# ThreadModule.net
KiCad netlist of a schematic drawn in Altium Designer
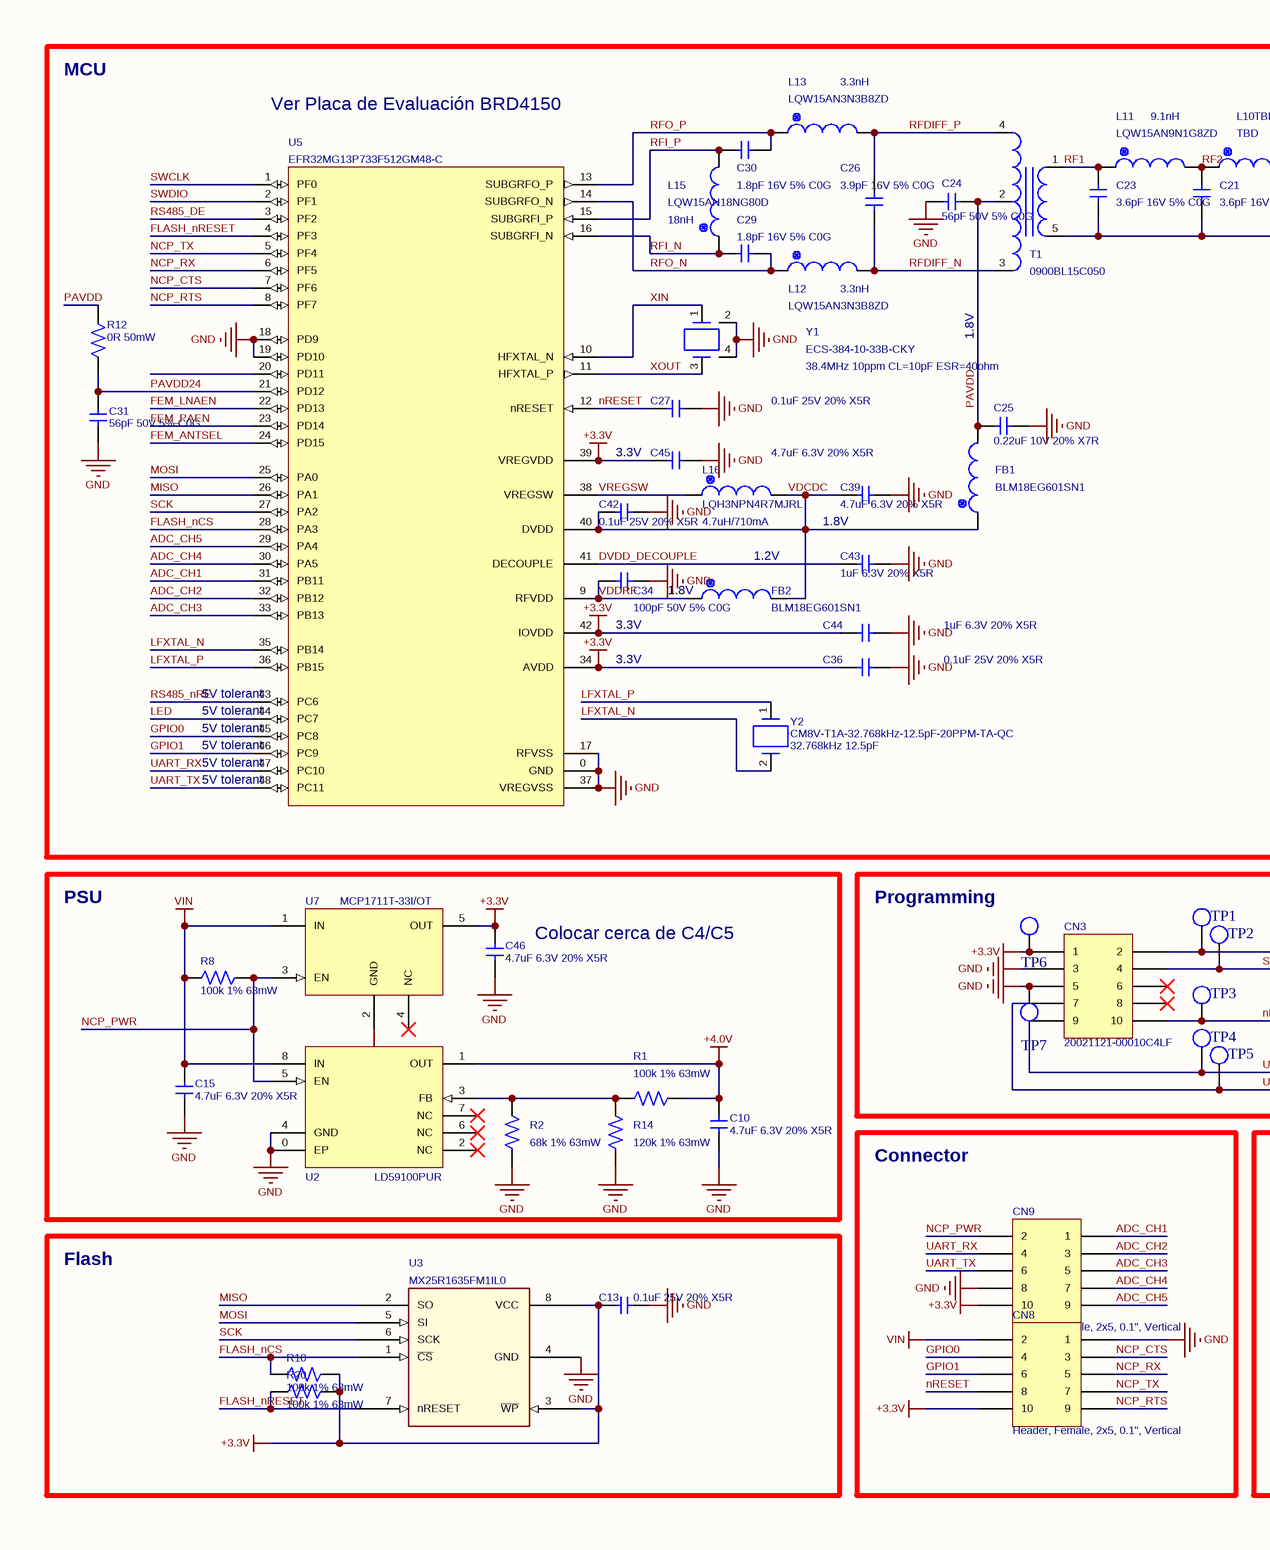
[diagram p0: ThreadModule.SchDoc, left]
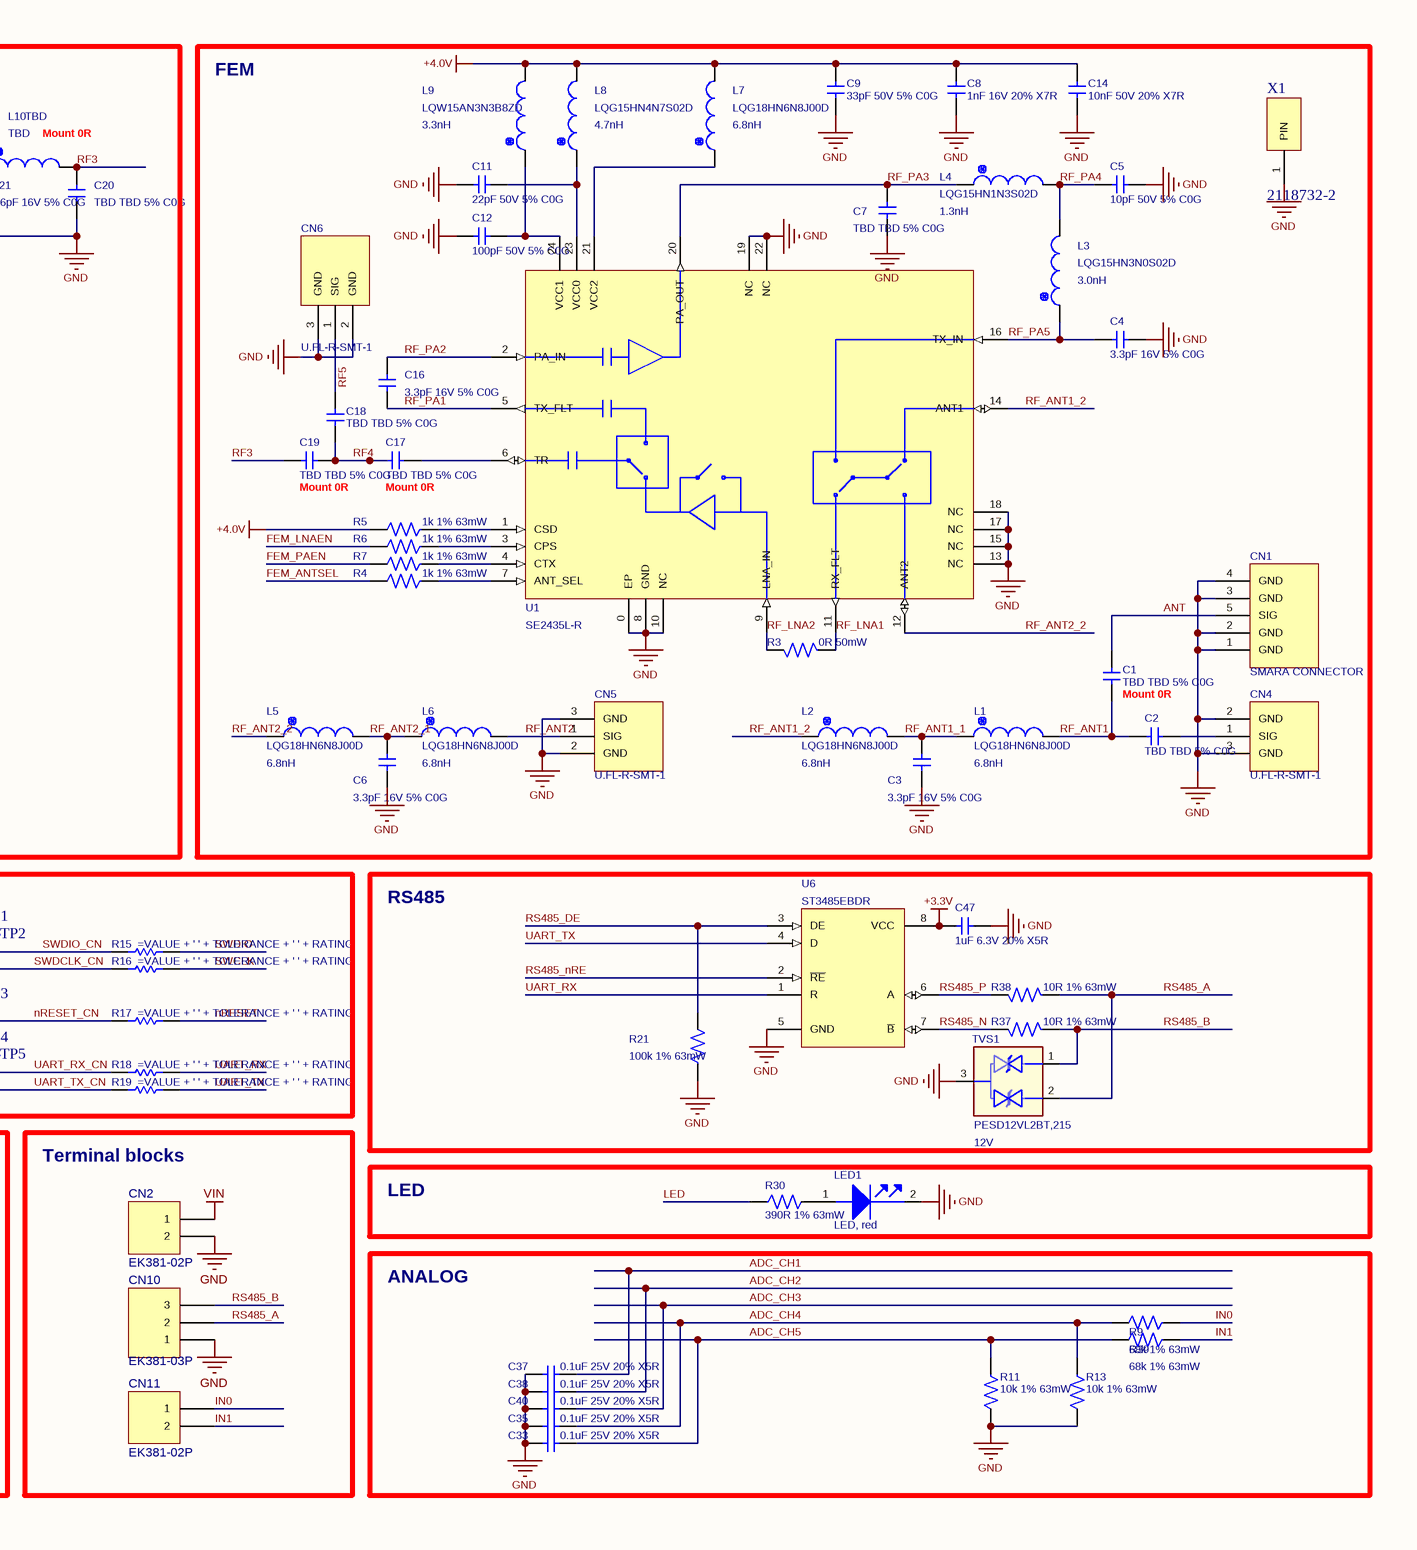
[diagram p1: ThreadModule.SchDoc, right]

(export (version "E")
  (design (tool "Eeschema 10.0.6"))
  (components
    (comp (ref "C1")
      (value "TBD TBD 5% C0G")
      (footprint "CAPC1005X55L")
      (description "Capacitor, ceramic")
      (fields
        (field (name "MFG") "<GENERIC>")
        (field (name "ASSEMBLYCOMMENTS") "Mount 0R")
        (field (name "TOLERANCE") "5%")
        (field (name "FOOTPRINT CHECKED") "Assign OK, Footprint OK")
      )
      (libsource (lib "*") (part "C_Dup1"))
    )
    (comp (ref "C2")
      (value "TBD TBD 5% C0G")
      (footprint "CAPC1005X55L")
      (description "Capacitor, ceramic")
      (fields
        (field (name "MFG") "<GENERIC>")
        (field (name "TOLERANCE") "5%")
        (field (name "FOOTPRINT CHECKED") "Assign OK, Footprint OK")
      )
      (libsource (lib "*") (part "C_Dup1"))
    )
    (comp (ref "C3")
      (value "3.3pF 16V 5% C0G")
      (footprint "CAPC1005X55L")
      (description "Capacitor, ceramic")
      (fields
        (field (name "MFG") "YAGEO")
        (field (name "TOLERANCE") "5%")
        (field (name "FOOTPRINT CHECKED") "Assign OK, Footprint OK")
      )
      (libsource (lib "*") (part "C_Dup1"))
    )
    (comp (ref "C4")
      (value "3.3pF 16V 5% C0G")
      (footprint "CAPC1005X55L")
      (description "Capacitor, ceramic")
      (fields
        (field (name "MFG") "YAGEO")
        (field (name "TOLERANCE") "5%")
        (field (name "FOOTPRINT CHECKED") "Assign OK, Footprint OK")
      )
      (libsource (lib "*") (part "C_Dup1"))
    )
    (comp (ref "C5")
      (value "10pF 50V 5% C0G")
      (footprint "CAPC1005X55L")
      (description "Capacitor, ceramic")
      (fields
        (field (name "MFG") "SAMSUNG")
        (field (name "TOLERANCE") "5%")
        (field (name "FOOTPRINT CHECKED") "Assign OK, Footprint OK")
      )
      (libsource (lib "*") (part "C_Dup1"))
    )
    (comp (ref "C6")
      (value "3.3pF 16V 5% C0G")
      (footprint "CAPC1005X55L")
      (description "Capacitor, ceramic")
      (fields
        (field (name "MFG") "YAGEO")
        (field (name "TOLERANCE") "5%")
        (field (name "FOOTPRINT CHECKED") "Assign OK, Footprint OK")
      )
      (libsource (lib "*") (part "C_Dup1"))
    )
    (comp (ref "C7")
      (value "TBD TBD 5% C0G")
      (footprint "CAPC1005X55L")
      (description "Capacitor, ceramic")
      (fields
        (field (name "MFG") "<GENERIC>")
        (field (name "TOLERANCE") "5%")
        (field (name "FOOTPRINT CHECKED") "Assign OK, Footprint OK")
      )
      (libsource (lib "*") (part "C_Dup1"))
    )
    (comp (ref "C8")
      (value "1nF 16V 20% X7R")
      (footprint "CAPC1005X55L")
      (description "Capacitor, ceramic")
      (fields
        (field (name "MFG") "SAMSUNG")
        (field (name "TOLERANCE") "20%")
        (field (name "FOOTPRINT CHECKED") "Assign OK, Footprint OK")
      )
      (libsource (lib "*") (part "C_Dup1"))
    )
    (comp (ref "C9")
      (value "33pF 50V 5% C0G")
      (footprint "CAPC1005X55L")
      (description "Capacitor, ceramic")
      (fields
        (field (name "MFG") "SAMSUNG")
        (field (name "TOLERANCE") "5%")
        (field (name "FOOTPRINT CHECKED") "Assign OK, Footprint OK")
      )
      (libsource (lib "*") (part "C_Dup1"))
    )
    (comp (ref "C10")
      (value "4.7uF 6.3V 20% X5R")
      (footprint "CAPC1608X90N")
      (description "Capacitor, ceramic")
      (fields
        (field (name "MFG") "SAMSUNG")
        (field (name "TOLERANCE") "20%")
        (field (name "FOOTPRINT CHECKED") "Assign OK, Footprint OK")
      )
      (libsource (lib "*") (part "C_Dup1"))
    )
    (comp (ref "C11")
      (value "22pF 50V 5% C0G")
      (footprint "CAPC1005X55L")
      (description "Capacitor, ceramic")
      (fields
        (field (name "MFG") "SAMSUNG")
        (field (name "TOLERANCE") "5%")
        (field (name "FOOTPRINT CHECKED") "Assign OK, Footprint OK")
      )
      (libsource (lib "*") (part "C_Dup1"))
    )
    (comp (ref "C12")
      (value "100pF 50V 5% C0G")
      (footprint "CAPC1005X55L")
      (description "Capacitor, ceramic")
      (fields
        (field (name "MFG") "SAMSUNG")
        (field (name "TOLERANCE") "5%")
        (field (name "FOOTPRINT CHECKED") "Assign OK, Footprint OK")
      )
      (libsource (lib "*") (part "C_Dup1"))
    )
    (comp (ref "C13")
      (value "0.1uF 25V 20% X5R")
      (footprint "CAPC1005N")
      (description "Capacitor, ceramic")
      (fields
        (field (name "MFG") "SAMSUNG")
        (field (name "TOLERANCE") "20%")
        (field (name "FOOTPRINT CHECKED") "Assign OK, Footprint OK")
      )
      (libsource (lib "*") (part "C_Dup1"))
    )
    (comp (ref "C14")
      (value "10nF 50V 20% X7R")
      (footprint "CAPC1005X55L")
      (description "Capacitor, ceramic")
      (fields
        (field (name "MFG") "SAMSUNG")
        (field (name "TOLERANCE") "20%")
        (field (name "FOOTPRINT CHECKED") "Assign OK, Footprint OK")
      )
      (libsource (lib "*") (part "C_Dup1"))
    )
    (comp (ref "C15")
      (value "4.7uF 6.3V 20% X5R")
      (footprint "CAPC1608X90N")
      (description "Capacitor, ceramic")
      (fields
        (field (name "MFG") "SAMSUNG")
        (field (name "TOLERANCE") "20%")
        (field (name "FOOTPRINT CHECKED") "Assign OK, Footprint OK")
      )
      (libsource (lib "*") (part "C_Dup1"))
    )
    (comp (ref "C16")
      (value "3.3pF 16V 5% C0G")
      (footprint "CAPC1005X55L")
      (description "Capacitor, ceramic")
      (fields
        (field (name "MFG") "YAGEO")
        (field (name "TOLERANCE") "5%")
        (field (name "FOOTPRINT CHECKED") "Assign OK, Footprint OK")
      )
      (libsource (lib "*") (part "C_Dup1"))
    )
    (comp (ref "C17")
      (value "TBD TBD 5% C0G")
      (footprint "CAPC1005X55L")
      (description "Capacitor, ceramic")
      (fields
        (field (name "MFG") "<GENERIC>")
        (field (name "ASSEMBLYCOMMENTS") "Mount 0R")
        (field (name "TOLERANCE") "5%")
        (field (name "FOOTPRINT CHECKED") "Assign OK, Footprint OK")
      )
      (libsource (lib "*") (part "C_Dup1"))
    )
    (comp (ref "C18")
      (value "TBD TBD 5% C0G")
      (footprint "CAPC1005X55L")
      (description "Capacitor, ceramic")
      (fields
        (field (name "MFG") "<GENERIC>")
        (field (name "TOLERANCE") "5%")
        (field (name "FOOTPRINT CHECKED") "Assign OK, Footprint OK")
      )
      (libsource (lib "*") (part "C_Dup1"))
    )
    (comp (ref "C19")
      (value "TBD TBD 5% C0G")
      (footprint "CAPC1005X55L")
      (description "Capacitor, ceramic")
      (fields
        (field (name "MFG") "<GENERIC>")
        (field (name "ASSEMBLYCOMMENTS") "Mount 0R")
        (field (name "TOLERANCE") "5%")
        (field (name "FOOTPRINT CHECKED") "Assign OK, Footprint OK")
      )
      (libsource (lib "*") (part "C_Dup1"))
    )
    (comp (ref "C20")
      (value "TBD TBD 5% C0G")
      (footprint "CAPC1005X55L")
      (description "Capacitor, ceramic")
      (fields
        (field (name "MFG") "<GENERIC>")
        (field (name "TOLERANCE") "5%")
        (field (name "FOOTPRINT CHECKED") "Assign OK, Footprint OK")
      )
      (libsource (lib "*") (part "C_Dup1"))
    )
    (comp (ref "C21")
      (value "3.6pF 16V 5% C0G")
      (footprint "CAPC1005X55L")
      (description "Capacitor, ceramic")
      (fields
        (field (name "MFG") "YAGEO")
        (field (name "TOLERANCE") "5%")
        (field (name "FOOTPRINT CHECKED") "Assign OK, Footprint OK")
      )
      (libsource (lib "*") (part "C_Dup1"))
    )
    (comp (ref "C23")
      (value "3.6pF 16V 5% C0G")
      (footprint "CAPC1005X55L")
      (description "Capacitor, ceramic")
      (fields
        (field (name "MFG") "YAGEO")
        (field (name "TOLERANCE") "5%")
        (field (name "FOOTPRINT CHECKED") "Assign OK, Footprint OK")
      )
      (libsource (lib "*") (part "C_Dup1"))
    )
    (comp (ref "C24")
      (value "56pF 50V 5% C0G")
      (footprint "CAPC1005X55L")
      (description "Capacitor, ceramic")
      (fields
        (field (name "MFG") "SAMSUNG")
        (field (name "TOLERANCE") "5%")
        (field (name "FOOTPRINT CHECKED") "Assign OK, Footprint OK")
      )
      (libsource (lib "*") (part "C_Dup1"))
    )
    (comp (ref "C25")
      (value "0.22uF 10V 20% X7R")
      (footprint "CAPC1005N")
      (description "Capacitor, ceramic")
      (fields
        (field (name "MFG") "SAMSUNG")
        (field (name "TOLERANCE") "20%")
        (field (name "FOOTPRINT CHECKED") "Assign OK, Footprint OK")
      )
      (libsource (lib "*") (part "C_Dup1"))
    )
    (comp (ref "C26")
      (value "3.9pF 16V 5% C0G")
      (footprint "CAPC1005X55L")
      (description "Capacitor, ceramic")
      (fields
        (field (name "MFG") "YAGEO")
        (field (name "TOLERANCE") "5%")
        (field (name "FOOTPRINT CHECKED") "Assign OK, Footprint OK")
      )
      (libsource (lib "*") (part "C_Dup1"))
    )
    (comp (ref "C27")
      (value "0.1uF 25V 20% X5R")
      (footprint "CAPC1005N")
      (description "Capacitor, ceramic")
      (fields
        (field (name "MFG") "SAMSUNG")
        (field (name "TOLERANCE") "20%")
        (field (name "FOOTPRINT CHECKED") "Assign OK, Footprint OK")
      )
      (libsource (lib "*") (part "C_Dup1"))
    )
    (comp (ref "C29")
      (value "1.8pF 16V 5% C0G")
      (footprint "CAPC1005X55L")
      (description "Capacitor, ceramic")
      (fields
        (field (name "MFG") "YAGEO")
        (field (name "TOLERANCE") "5%")
        (field (name "FOOTPRINT CHECKED") "Assign OK, Footprint OK")
      )
      (libsource (lib "*") (part "C_Dup1"))
    )
    (comp (ref "C30")
      (value "1.8pF 16V 5% C0G")
      (footprint "CAPC1005X55L")
      (description "Capacitor, ceramic")
      (fields
        (field (name "MFG") "YAGEO")
        (field (name "TOLERANCE") "5%")
        (field (name "FOOTPRINT CHECKED") "Assign OK, Footprint OK")
      )
      (libsource (lib "*") (part "C_Dup1"))
    )
    (comp (ref "C31")
      (value "56pF 50V 5% C0G")
      (footprint "CAPC1005X55L")
      (description "Capacitor, ceramic")
      (fields
        (field (name "MFG") "SAMSUNG")
        (field (name "TOLERANCE") "5%")
        (field (name "FOOTPRINT CHECKED") "Assign OK, Footprint OK")
      )
      (libsource (lib "*") (part "C_Dup1"))
    )
    (comp (ref "C33")
      (value "0.1uF 25V 20% X5R")
      (footprint "CAPC1005N")
      (description "Capacitor, ceramic")
      (fields
        (field (name "MFG") "SAMSUNG")
        (field (name "TOLERANCE") "20%")
        (field (name "FOOTPRINT CHECKED") "Assign OK, Footprint OK")
      )
      (libsource (lib "*") (part "C_Dup1"))
    )
    (comp (ref "C34")
      (value "100pF 50V 5% C0G")
      (footprint "CAPC1005X55L")
      (description "Capacitor, ceramic")
      (fields
        (field (name "MFG") "SAMSUNG")
        (field (name "TOLERANCE") "5%")
        (field (name "FOOTPRINT CHECKED") "Assign OK, Footprint OK")
      )
      (libsource (lib "*") (part "C_Dup1"))
    )
    (comp (ref "C35")
      (value "0.1uF 25V 20% X5R")
      (footprint "CAPC1005N")
      (description "Capacitor, ceramic")
      (fields
        (field (name "MFG") "SAMSUNG")
        (field (name "TOLERANCE") "20%")
        (field (name "FOOTPRINT CHECKED") "Assign OK, Footprint OK")
      )
      (libsource (lib "*") (part "C_Dup1"))
    )
    (comp (ref "C36")
      (value "0.1uF 25V 20% X5R")
      (footprint "CAPC1005N")
      (description "Capacitor, ceramic")
      (fields
        (field (name "MFG") "SAMSUNG")
        (field (name "TOLERANCE") "20%")
        (field (name "FOOTPRINT CHECKED") "Assign OK, Footprint OK")
      )
      (libsource (lib "*") (part "C_Dup1"))
    )
    (comp (ref "C37")
      (value "0.1uF 25V 20% X5R")
      (footprint "CAPC1005N")
      (description "Capacitor, ceramic")
      (fields
        (field (name "MFG") "SAMSUNG")
        (field (name "TOLERANCE") "20%")
        (field (name "FOOTPRINT CHECKED") "Assign OK, Footprint OK")
      )
      (libsource (lib "*") (part "C_Dup1"))
    )
    (comp (ref "C38")
      (value "0.1uF 25V 20% X5R")
      (footprint "CAPC1005N")
      (description "Capacitor, ceramic")
      (fields
        (field (name "MFG") "SAMSUNG")
        (field (name "TOLERANCE") "20%")
        (field (name "FOOTPRINT CHECKED") "Assign OK, Footprint OK")
      )
      (libsource (lib "*") (part "C_Dup1"))
    )
    (comp (ref "C39")
      (value "4.7uF 6.3V 20% X5R")
      (footprint "CAPC1608X90N")
      (description "Capacitor, ceramic")
      (fields
        (field (name "MFG") "SAMSUNG")
        (field (name "TOLERANCE") "20%")
        (field (name "FOOTPRINT CHECKED") "Assign OK, Footprint OK")
      )
      (libsource (lib "*") (part "C_Dup1"))
    )
    (comp (ref "C40")
      (value "0.1uF 25V 20% X5R")
      (footprint "CAPC1005N")
      (description "Capacitor, ceramic")
      (fields
        (field (name "MFG") "SAMSUNG")
        (field (name "TOLERANCE") "20%")
        (field (name "FOOTPRINT CHECKED") "Assign OK, Footprint OK")
      )
      (libsource (lib "*") (part "C_Dup1"))
    )
    (comp (ref "C42")
      (value "0.1uF 25V 20% X5R")
      (footprint "CAPC1005N")
      (description "Capacitor, ceramic")
      (fields
        (field (name "MFG") "SAMSUNG")
        (field (name "TOLERANCE") "20%")
        (field (name "FOOTPRINT CHECKED") "Assign OK, Footprint OK")
      )
      (libsource (lib "*") (part "C_Dup1"))
    )
    (comp (ref "C43")
      (value "1uF 6.3V 20% X5R")
      (footprint "CAPC1005N")
      (description "Capacitor, ceramic")
      (fields
        (field (name "MFG") "SAMSUNG")
        (field (name "TOLERANCE") "20%")
        (field (name "FOOTPRINT CHECKED") "Assign OK, Footprint OK")
      )
      (libsource (lib "*") (part "C_Dup1"))
    )
    (comp (ref "C44")
      (value "1uF 6.3V 20% X5R")
      (footprint "CAPC1005N")
      (description "Capacitor, ceramic")
      (fields
        (field (name "MFG") "SAMSUNG")
        (field (name "TOLERANCE") "20%")
        (field (name "FOOTPRINT CHECKED") "Assign OK, Footprint OK")
      )
      (libsource (lib "*") (part "C_Dup1"))
    )
    (comp (ref "C45")
      (value "4.7uF 6.3V 20% X5R")
      (footprint "CAPC1608X90N")
      (description "Capacitor, ceramic")
      (fields
        (field (name "MFG") "SAMSUNG")
        (field (name "TOLERANCE") "20%")
        (field (name "FOOTPRINT CHECKED") "Assign OK, Footprint OK")
      )
      (libsource (lib "*") (part "C_Dup1"))
    )
    (comp (ref "C46")
      (value "4.7uF 6.3V 20% X5R")
      (footprint "CAPC1608X90N")
      (description "Capacitor, ceramic")
      (fields
        (field (name "MFG") "SAMSUNG")
        (field (name "TOLERANCE") "20%")
        (field (name "FOOTPRINT CHECKED") "Assign OK, Footprint OK")
      )
      (libsource (lib "*") (part "C_Dup1"))
    )
    (comp (ref "C47")
      (value "1uF 6.3V 20% X5R")
      (footprint "CAPC1005N")
      (description "Capacitor, ceramic")
      (fields
        (field (name "MFG") "SAMSUNG")
        (field (name "TOLERANCE") "20%")
        (field (name "FOOTPRINT CHECKED") "Assign OK, Footprint OK")
      )
      (libsource (lib "*") (part "C_Dup1"))
    )
    (comp (ref "CN1")
      (value "SMARA CONNECTOR")
      (footprint "0733910320")
      (description "SMA, Right angle")
      (fields (field (name "MFG") "LPRS") (field (name "FOOTPRINT CHECKED") "Assign OK, Footprint OK"))
      (libsource (lib "xct") (part "RPSMA"))
    )
    (comp (ref "CN2")
      (value "EK381-02P")
      (footprint "EK381-02P")
      (description "Header, 2-Pin")
      (fields (field (name "MFG") "DINKLE") (field (name "FOOTPRINT CHECKED") "Assign OK, Footprint OK"))
      (libsource (lib "Miscellaneous Connectors") (part "Header 2"))
    )
    (comp (ref "CN3")
      (value "20021121-00010C4LF")
      (footprint "SensorWireless:HDR2X5")
      (description "Connector Header Surface Mount 10 position 0.050\" (1.27mm)")
      (fields (field (name "MFG") "AMPHENOL") (field (name "FOOTPRINT CHECKED") "Assign Ok, Footprint Ok"))
      (libsource (lib "Miscellaneous Connectors") (part "Header 5X2"))
    )
    (comp (ref "CN4")
      (value "U.FL-R-SMT-1")
      (footprint "U.FL-R-SMT-1")
      (description "Ultra Small Surface Mount Coaxial Connectors - 1.9mm or 2.4mm Mated Height")
      (fields (field (name "MFG") "HIROSE") (field (name "FOOTPRINT CHECKED") "Assign OK, Footprint OK"))
      (libsource (lib "traz") (part "U.FL-R-SMT-1"))
    )
    (comp (ref "CN5")
      (value "U.FL-R-SMT-1")
      (footprint "U.FL-R-SMT-1")
      (description "Ultra Small Surface Mount Coaxial Connectors - 1.9mm or 2.4mm Mated Height")
      (fields (field (name "MFG") "HIROSE") (field (name "FOOTPRINT CHECKED") "Assign OK, Footprint OK"))
      (libsource (lib "") (part "U.FL-R-SMT-1_1"))
    )
    (comp (ref "CN6")
      (value "U.FL-R-SMT-1")
      (footprint "U.FL-R-SMT-1")
      (description "Ultra Small Surface Mount Coaxial Connectors - 1.9mm or 2.4mm Mated Height")
      (fields (field (name "MFG") "HIROSE") (field (name "FOOTPRINT CHECKED") "Assign OK, Footprint OK"))
      (libsource (lib "traz") (part "U.FL-R-SMT-1"))
    )
    (comp (ref "CN8")
      (value "Header, Female, 2x5, 0.1\", Vertical")
      (fields (field (name "MFG") "<GENERIC>") (field (name "FOOTPRINT CHECKED") "Assign Ok, Footprint Ok"))
      (libsource (lib "") (part "Header 5X2_1"))
    )
    (comp (ref "CN9")
      (value "Header, Female, 2x5, 0.1\", Vertical")
      (fields (field (name "MFG") "<GENERIC>") (field (name "FOOTPRINT CHECKED") "Assign Ok, Footprint Ok"))
      (libsource (lib "") (part "Header 5X2_1"))
    )
    (comp (ref "CN10")
      (value "EK381-03P")
      (footprint "EK381-03P")
      (description "Header, 3-Pin")
      (fields (field (name "MFG") "DINKLE") (field (name "FOOTPRINT CHECKED") "Assign OK, Footprint OK"))
      (libsource (lib "Miscellaneous Connectors") (part "Header 3"))
    )
    (comp (ref "CN11")
      (value "EK381-02P")
      (footprint "EK381-02P")
      (description "Header, 2-Pin")
      (fields (field (name "MFG") "DINKLE") (field (name "FOOTPRINT CHECKED") "Assign OK, Footprint OK"))
      (libsource (lib "Miscellaneous Connectors") (part "Header 2"))
    )
    (comp (ref "FB1")
      (value "BLM18EG601SN1")
      (footprint "INDC1608X95N")
      (description "Ferrite bead")
      (fields (field (name "MFG") "MURATA") (field (name "FOOTPRINT CHECKED") "Assign OK, Footprint OK"))
      (libsource (lib "*") (part "L"))
    )
    (comp (ref "FB2")
      (value "BLM18EG601SN1")
      (footprint "INDC1608X95N")
      (description "Ferrite bead")
      (fields (field (name "MFG") "MURATA") (field (name "FOOTPRINT CHECKED") "Assign OK, Footprint OK"))
      (libsource (lib "*") (part "L"))
    )
    (comp (ref "L1")
      (value "LQG18HN6N8J00D")
      (footprint "INDC1608X95N")
      (description "Inductor")
      (fields
        (field (name "MFG") "MURATA")
        (field (name "ALTIUM_VALUE") "6.8nH")
        (field (name "TOLERANCE") "TBD%")
        (field (name "FOOTPRINT CHECKED") "Assign OK, Footprint OK")
      )
      (libsource (lib "*") (part "L"))
    )
    (comp (ref "L2")
      (value "LQG18HN6N8J00D")
      (footprint "INDC1608X95N")
      (description "Inductor")
      (fields
        (field (name "MFG") "MURATA")
        (field (name "ALTIUM_VALUE") "6.8nH")
        (field (name "TOLERANCE") "TBD%")
        (field (name "FOOTPRINT CHECKED") "Assign OK, Footprint OK")
      )
      (libsource (lib "*") (part "L"))
    )
    (comp (ref "L3")
      (value "LQG15HN3N0S02D")
      (footprint "INDC1005X55L")
      (description "Inductor")
      (fields
        (field (name "MFG") "MURATA")
        (field (name "ALTIUM_VALUE") "3.0nH")
        (field (name "TOLERANCE") "TBD%")
        (field (name "FOOTPRINT CHECKED") "Assign OK, Footprint OK")
      )
      (libsource (lib "*") (part "L"))
    )
    (comp (ref "L4")
      (value "LQG15HN1N3S02D")
      (footprint "INDC1005X55L")
      (description "Inductor")
      (fields
        (field (name "MFG") "MURATA")
        (field (name "ALTIUM_VALUE") "1.3nH")
        (field (name "TOLERANCE") "TBD%")
        (field (name "FOOTPRINT CHECKED") "Assign OK, Footprint OK")
      )
      (libsource (lib "*") (part "L"))
    )
    (comp (ref "L5")
      (value "LQG18HN6N8J00D")
      (footprint "INDC1608X95N")
      (description "Inductor")
      (fields
        (field (name "MFG") "MURATA")
        (field (name "ALTIUM_VALUE") "6.8nH")
        (field (name "TOLERANCE") "TBD%")
        (field (name "FOOTPRINT CHECKED") "Assign OK, Footprint OK")
      )
      (libsource (lib "*") (part "L"))
    )
    (comp (ref "L6")
      (value "LQG18HN6N8J00D")
      (footprint "INDC1608X95N")
      (description "Inductor")
      (fields
        (field (name "MFG") "MURATA")
        (field (name "ALTIUM_VALUE") "6.8nH")
        (field (name "TOLERANCE") "TBD%")
        (field (name "FOOTPRINT CHECKED") "Assign OK, Footprint OK")
      )
      (libsource (lib "*") (part "L"))
    )
    (comp (ref "L7")
      (value "LQG18HN6N8J00D")
      (footprint "INDC1608X95N")
      (description "Inductor")
      (fields
        (field (name "MFG") "MURATA")
        (field (name "ALTIUM_VALUE") "6.8nH")
        (field (name "TOLERANCE") "TBD%")
        (field (name "FOOTPRINT CHECKED") "Assign OK, Footprint OK")
      )
      (libsource (lib "*") (part "L"))
    )
    (comp (ref "L8")
      (value "LQG15HN4N7S02D")
      (footprint "INDC1005X55L")
      (description "Inductor")
      (fields
        (field (name "MFG") "MURATA")
        (field (name "ALTIUM_VALUE") "4.7nH")
        (field (name "TOLERANCE") "TBD%")
        (field (name "FOOTPRINT CHECKED") "Assign OK, Footprint OK")
      )
      (libsource (lib "*") (part "L"))
    )
    (comp (ref "L9")
      (value "LQW15AN3N3B8ZD")
      (footprint "INDC1005X55L")
      (description "Inductor")
      (fields
        (field (name "MFG") "MURATA")
        (field (name "ALTIUM_VALUE") "3.3nH")
        (field (name "TOLERANCE") "TBD%")
        (field (name "FOOTPRINT CHECKED") "Assign OK, Footprint OK")
      )
      (libsource (lib "*") (part "L"))
    )
    (comp (ref "L10")
      (value "TBD")
      (footprint "INDC1005X55L")
      (description "Inductor")
      (fields
        (field (name "ASSEMBLYCOMMENTS") "Mount 0R")
        (field (name "ALTIUM_VALUE") "TBD")
        (field (name "TOLERANCE") "TBD%")
        (field (name "FOOTPRINT CHECKED") "Assign OK, Footprint OK")
      )
      (libsource (lib "*") (part "L"))
    )
    (comp (ref "L11")
      (value "LQW15AN9N1G8ZD")
      (footprint "INDC1005X55L")
      (description "Inductor")
      (fields
        (field (name "MFG") "MURATA")
        (field (name "ALTIUM_VALUE") "9.1nH")
        (field (name "TOLERANCE") "TBD%")
        (field (name "FOOTPRINT CHECKED") "Assign OK, Footprint OK")
      )
      (libsource (lib "*") (part "L"))
    )
    (comp (ref "L12")
      (value "LQW15AN3N3B8ZD")
      (footprint "INDC1005X55L")
      (description "Inductor")
      (fields
        (field (name "MFG") "MURATA")
        (field (name "ALTIUM_VALUE") "3.3nH")
        (field (name "TOLERANCE") "TBD%")
        (field (name "FOOTPRINT CHECKED") "Assign OK, Footprint OK")
      )
      (libsource (lib "*") (part "L"))
    )
    (comp (ref "L13")
      (value "LQW15AN3N3B8ZD")
      (footprint "INDC1005X55L")
      (description "Inductor")
      (fields
        (field (name "MFG") "MURATA")
        (field (name "ALTIUM_VALUE") "3.3nH")
        (field (name "TOLERANCE") "TBD%")
        (field (name "FOOTPRINT CHECKED") "Assign OK, Footprint OK")
      )
      (libsource (lib "*") (part "L"))
    )
    (comp (ref "L15")
      (value "LQW15AN18NG80D")
      (footprint "INDC1005X55L")
      (description "Inductor")
      (fields
        (field (name "MFG") "MURATA")
        (field (name "ALTIUM_VALUE") "18nH")
        (field (name "TOLERANCE") "TBD%")
        (field (name "FOOTPRINT CHECKED") "Assign OK, Footprint OK")
      )
      (libsource (lib "*") (part "L"))
    )
    (comp (ref "L16")
      (value "LQH3NPN4R7MJRL")
      (footprint "INDW3030N")
      (description "Inductor")
      (fields
        (field (name "MFG") "MURATA")
        (field (name "ALTIUM_VALUE") "4.7uH/710mA")
        (field (name "TOLERANCE") "TBD%")
        (field (name "FOOTPRINT CHECKED") "Assign OK, Footprint OK")
      )
      (libsource (lib "*") (part "L"))
    )
    (comp (ref "LED1")
      (value "LED, red")
      (footprint "LEDC2012N")
      (fields (field (name "MFG") "<GENERIC>") (field (name "FOOTPRINT CHECKED") "Assign OK, Footprint OK"))
      (libsource (lib "*") (part "Led Red HSMC-C170"))
    )
    (comp (ref "R1")
      (value "100k 1% 63mW")
      (footprint "RESC1608X40N")
      (description "Resistor, SMD")
      (fields
        (field (name "MFG") "<GENERIC>")
        (field (name "TOLERANCE") "1%")
        (field (name "FOOTPRINT CHECKED") "Assign OK, Footprint OK")
      )
      (libsource (lib "*") (part "R"))
    )
    (comp (ref "R2")
      (value "68k 1% 63mW")
      (footprint "RESC1608X40N")
      (description "Resistor, SMD")
      (fields
        (field (name "MFG") "<GENERIC>")
        (field (name "TOLERANCE") "1%")
        (field (name "FOOTPRINT CHECKED") "Assign OK, Footprint OK")
      )
      (libsource (lib "*") (part "R"))
    )
    (comp (ref "R3")
      (value "0R 50mW")
      (footprint "RESC1005X40N")
      (description "Resistor, SMD")
      (fields
        (field (name "MFG") "<GENERIC>")
        (field (name "POWER") "50mW")
        (field (name "FOOTPRINT CHECKED") "Assign OK, Footprint OK")
      )
      (libsource (lib "*") (part "R"))
    )
    (comp (ref "R4")
      (value "1k 1% 63mW")
      (footprint "RESC1608X40N")
      (description "Resistor, SMD")
      (fields
        (field (name "MFG") "<GENERIC>")
        (field (name "TOLERANCE") "1%")
        (field (name "FOOTPRINT CHECKED") "Assign OK, Footprint OK")
      )
      (libsource (lib "*") (part "R"))
    )
    (comp (ref "R5")
      (value "1k 1% 63mW")
      (footprint "RESC1608X40N")
      (description "Resistor, SMD")
      (fields
        (field (name "MFG") "<GENERIC>")
        (field (name "TOLERANCE") "1%")
        (field (name "FOOTPRINT CHECKED") "Assign OK, Footprint OK")
      )
      (libsource (lib "*") (part "R"))
    )
    (comp (ref "R6")
      (value "1k 1% 63mW")
      (footprint "RESC1608X40N")
      (description "Resistor, SMD")
      (fields
        (field (name "MFG") "<GENERIC>")
        (field (name "TOLERANCE") "1%")
        (field (name "FOOTPRINT CHECKED") "Assign OK, Footprint OK")
      )
      (libsource (lib "*") (part "R"))
    )
    (comp (ref "R7")
      (value "1k 1% 63mW")
      (footprint "RESC1608X40N")
      (description "Resistor, SMD")
      (fields
        (field (name "MFG") "<GENERIC>")
        (field (name "TOLERANCE") "1%")
        (field (name "FOOTPRINT CHECKED") "Assign OK, Footprint OK")
      )
      (libsource (lib "*") (part "R"))
    )
    (comp (ref "R8")
      (value "100k 1% 63mW")
      (footprint "RESC1608X40N")
      (description "Resistor, SMD")
      (fields
        (field (name "MFG") "<GENERIC>")
        (field (name "TOLERANCE") "1%")
        (field (name "FOOTPRINT CHECKED") "Assign OK, Footprint OK")
      )
      (libsource (lib "*") (part "R"))
    )
    (comp (ref "R9")
      (value "68k 1% 63mW")
      (footprint "RESC1608X40N")
      (description "Resistor, SMD")
      (fields
        (field (name "MFG") "<GENERIC>")
        (field (name "TOLERANCE") "1%")
        (field (name "FOOTPRINT CHECKED") "Assign OK, Footprint OK")
      )
      (libsource (lib "*") (part "R"))
    )
    (comp (ref "R10")
      (value "100k 1% 63mW")
      (footprint "RESC1608X40N")
      (description "Resistor, SMD")
      (fields
        (field (name "MFG") "<GENERIC>")
        (field (name "TOLERANCE") "1%")
        (field (name "FOOTPRINT CHECKED") "Assign OK, Footprint OK")
      )
      (libsource (lib "*") (part "R"))
    )
    (comp (ref "R11")
      (value "10k 1% 63mW")
      (footprint "RESC1608X40N")
      (description "Resistor, SMD")
      (fields
        (field (name "MFG") "<GENERIC>")
        (field (name "TOLERANCE") "1%")
        (field (name "FOOTPRINT CHECKED") "Assign OK, Footprint OK")
      )
      (libsource (lib "*") (part "R"))
    )
    (comp (ref "R12")
      (value "0R 50mW")
      (footprint "RESC1005X40N")
      (description "Resistor, SMD")
      (fields
        (field (name "MFG") "<GENERIC>")
        (field (name "POWER") "50mW")
        (field (name "FOOTPRINT CHECKED") "Assign OK, Footprint OK")
      )
      (libsource (lib "*") (part "R"))
    )
    (comp (ref "R13")
      (value "10k 1% 63mW")
      (footprint "RESC1608X40N")
      (description "Resistor, SMD")
      (fields
        (field (name "MFG") "<GENERIC>")
        (field (name "TOLERANCE") "1%")
        (field (name "FOOTPRINT CHECKED") "Assign OK, Footprint OK")
      )
      (libsource (lib "*") (part "R"))
    )
    (comp (ref "R14")
      (value "120k 1% 63mW")
      (footprint "RESC1608X40N")
      (description "Resistor, SMD")
      (fields
        (field (name "MFG") "<GENERIC>")
        (field (name "TOLERANCE") "1%")
        (field (name "FOOTPRINT CHECKED") "Assign OK, Footprint OK")
      )
      (libsource (lib "*") (part "R"))
    )
    (comp (ref "R15")
      (value "47R 1%")
      (footprint "RESC1608X40N")
      (description "Resistor, SMD")
      (fields
        (field (name "MFG") "<GENERIC>")
        (field (name "TOLERANCE") "1%")
        (field (name "FOOTPRINT CHECKED") "Assign Ok, Footprint Ok")
      )
      (libsource (lib "SensorWireless") (part "RES"))
    )
    (comp (ref "R16")
      (value "47R 1%")
      (footprint "RESC1608X40N")
      (description "Resistor, SMD")
      (fields
        (field (name "MFG") "<GENERIC>")
        (field (name "TOLERANCE") "1%")
        (field (name "FOOTPRINT CHECKED") "Assign Ok, Footprint Ok")
      )
      (libsource (lib "SensorWireless") (part "RES"))
    )
    (comp (ref "R17")
      (value "47R 1%")
      (footprint "RESC1608X40N")
      (description "Resistor, SMD")
      (fields
        (field (name "MFG") "<GENERIC>")
        (field (name "TOLERANCE") "1%")
        (field (name "FOOTPRINT CHECKED") "Assign Ok, Footprint Ok")
      )
      (libsource (lib "SensorWireless") (part "RES"))
    )
    (comp (ref "R18")
      (value "47R 1%")
      (footprint "RESC1608X40N")
      (description "Resistor, SMD")
      (fields
        (field (name "MFG") "<GENERIC>")
        (field (name "TOLERANCE") "1%")
        (field (name "FOOTPRINT CHECKED") "Assign Ok, Footprint Ok")
      )
      (libsource (lib "SensorWireless") (part "RES"))
    )
    (comp (ref "R19")
      (value "47R 1%")
      (footprint "RESC1608X40N")
      (description "Resistor, SMD")
      (fields
        (field (name "MFG") "<GENERIC>")
        (field (name "TOLERANCE") "1%")
        (field (name "FOOTPRINT CHECKED") "Assign Ok, Footprint Ok")
      )
      (libsource (lib "SensorWireless") (part "RES"))
    )
    (comp (ref "R20")
      (value "100k 1% 63mW")
      (footprint "RESC1608X40N")
      (description "Resistor, SMD")
      (fields
        (field (name "MFG") "<GENERIC>")
        (field (name "TOLERANCE") "1%")
        (field (name "FOOTPRINT CHECKED") "Assign OK, Footprint OK")
      )
      (libsource (lib "*") (part "R"))
    )
    (comp (ref "R21")
      (value "100k 1% 63mW")
      (footprint "RESC1608X40N")
      (description "Resistor, SMD")
      (fields
        (field (name "MFG") "<GENERIC>")
        (field (name "TOLERANCE") "1%")
        (field (name "FOOTPRINT CHECKED") "Assign OK, Footprint OK")
      )
      (libsource (lib "*") (part "R"))
    )
    (comp (ref "R30")
      (value "390R 1% 63mW")
      (footprint "RESC1608X40N")
      (description "Resistor, SMD")
      (fields
        (field (name "MFG") "<GENERIC>")
        (field (name "TOLERANCE") "1%")
        (field (name "FOOTPRINT CHECKED") "Assign OK, Footprint OK")
      )
      (libsource (lib "*") (part "R"))
    )
    (comp (ref "R37")
      (value "10R 1% 63mW")
      (footprint "RESC1608X40N")
      (description "Resistor, SMD")
      (fields
        (field (name "MFG") "<GENERIC>")
        (field (name "TOLERANCE") "1%")
        (field (name "FOOTPRINT CHECKED") "Assign OK, Footprint OK")
      )
      (libsource (lib "*") (part "R"))
    )
    (comp (ref "R38")
      (value "10R 1% 63mW")
      (footprint "RESC1608X40N")
      (description "Resistor, SMD")
      (fields
        (field (name "MFG") "<GENERIC>")
        (field (name "TOLERANCE") "1%")
        (field (name "FOOTPRINT CHECKED") "Assign OK, Footprint OK")
      )
      (libsource (lib "*") (part "R"))
    )
    (comp (ref "R39")
      (value "68k 1% 63mW")
      (footprint "RESC1608X40N")
      (description "Resistor, SMD")
      (fields
        (field (name "MFG") "<GENERIC>")
        (field (name "TOLERANCE") "1%")
        (field (name "FOOTPRINT CHECKED") "Assign OK, Footprint OK")
      )
      (libsource (lib "*") (part "R"))
    )
    (comp (ref "T1")
      (value "0900BL15C050")
      (footprint "BALC2012")
      (description "50:50 ohms Balun")
      (fields (field (name "MFG") "JOHANSON") (field (name "FOOTPRINT CHECKED") "Assign OK, Footprint OK"))
      (libsource (lib "sch") (part "BALUN"))
    )
    (comp (ref "TP1") (value "Test point") (footprint "TP") (libsource (lib "SensorWireless") (part "TP")))
    (comp (ref "TP2") (value "Test point") (footprint "TP") (libsource (lib "SensorWireless") (part "TP")))
    (comp (ref "TP3") (value "Test point") (footprint "TP") (libsource (lib "SensorWireless") (part "TP")))
    (comp (ref "TP4") (value "Test point") (footprint "TP") (libsource (lib "SensorWireless") (part "TP")))
    (comp (ref "TP5") (value "Test point") (footprint "TP") (libsource (lib "SensorWireless") (part "TP")))
    (comp (ref "TP6") (value "Test point") (footprint "TP") (libsource (lib "SensorWireless") (part "TP")))
    (comp (ref "TP7") (value "Test point") (footprint "TP") (libsource (lib "SensorWireless") (part "TP")))
    (comp (ref "TVS1")
      (value "PESD12VL2BT,215")
      (footprint "SOT95P230X110-3N")
      (description "TVS array")
      (fields
        (field (name "MFG") "NXP")
        (field (name "ALTIUM_VALUE") "12V")
        (field (name "FOOTPRINT CHECKED") "Assign OK, Footprint OK")
      )
      (libsource (lib "diego") (part "NUP2105L"))
    )
    (comp (ref "U1")
      (value "SE2435L-R")
      (footprint "QFN50P400X400X90-25N")
      (description "860 to 930 MHz High-Power RF Front-End Module")
      (fields (field (name "MFG") "SKYWORKS") (field (name "FOOTPRINT CHECKED") "Assign OK, Footprint OK"))
      (libsource (lib "sch") (part "SE2435L"))
    )
    (comp (ref "U2")
      (value "LD59100PUR")
      (footprint "SON65P300X300X90-9N-2")
      (description "1A ultra low-dropout regulator with reverse current protection")
      (fields (field (name "MFG") "ST") (field (name "FOOTPRINT CHECKED") "Assign OK, Footprint OK"))
      (libsource (lib "sch") (part "LD59100"))
    )
    (comp (ref "U3")
      (value "MX25R1635FM1IL0")
      (footprint "SOIC127P600X175-8N")
      (description "2.5V/3.0V 16 Mbit Serial Quad I/O (SQI) Flash Memory")
      (fields (field (name "MFG") "MACRONIX") (field (name "FOOTPRINT CHECKED") "Assign OK, Footprint OK"))
      (libsource (lib "*") (part "AT45DB321C_CNC_0"))
    )
    (comp (ref "U5")
      (value "EFR32MG13P733F512GM48-C")
      (footprint "QFN50P700X700X100-49N")
      (description "Mighty Gecko Multi-Protocol Wireless SoC Family Data Sheet")
      (fields (field (name "MFG") "SILABS") (field (name "FOOTPRINT CHECKED") "Assign OK, Footprint OK"))
      (libsource (lib "sch") (part "EFR32xG1_2.4G_SUBGHZ_QFN48"))
    )
    (comp (ref "U6")
      (value "ST3485EBDR")
      (footprint "SOIC127P600X175-8N")
      (description "Differential Bus Transceiver")
      (fields (field (name "MFG") "ST") (field (name "FOOTPRINT CHECKED") "Assign OK, Footprint OK"))
      (libsource (lib "TI Interface Line Transceiver") (part "SN75176BD"))
    )
    (comp (ref "U7")
      (value "MCP1711T-33I/OT")
      (footprint "SensorWireless:SOT95P284X122-5N")
      (description "Linear Voltage Regulator IC  1 Output  150mA SOT-25-5")
      (fields (field (name "MFG") "MICROCHIP") (field (name "FOOTPRINT CHECKED") "Assign Ok, Footprint Ok"))
      (libsource (lib "SensorWireless") (part "XC6504"))
    )
    (comp (ref "X1")
      (value "2118732-2")
      (footprint "2118732")
      (description "RF SHIELD 1.5\" X 2\" SMD")
      (fields (field (name "MFG") "TE") (field (name "FOOTPRINT CHECKED") "Assign OK, Footprint OK"))
      (libsource (lib "sch") (part "NO_PINS"))
    )
    (comp (ref "Y1")
      (value "ECS-384-10-33B-CKY")
      (footprint "XTAL3225X60N")
      (description "Crystal")
      (fields
        (field (name "MFG") "ECS")
        (field (name "ALTIUM_VALUE") "38.4MHz 10ppm CL=10pF ESR=40ohm")
        (field (name "FOOTPRINT CHECKED") "Assign OK, Footprint OK")
      )
      (libsource (lib "sch") (part "CS10-12MHz"))
    )
    (comp (ref "Y2")
      (value "CM8V-T1A-32.768kHz-12.5pF-20PPM-TA-QC")
      (footprint "XTAL2.0x1.2")
      (description "Crystal")
      (fields
        (field (name "MFG") "MICRO CRYSTAL AG")
        (field (name "ALTIUM_VALUE") "32.768kHz 12.5pF")
        (field (name "FOOTPRINT CHECKED") "Assign OK, Footprint OK")
      )
      (libsource (lib "*") (part "CS10-12MHz"))
    )
  )
  (nets
    (net (code "1") (name "+3.3V") (class "Default")
      (node (ref "C13") (pin "1") (pinfunction "1_1") (pintype "passive"))
      (node (ref "C36") (pin "1") (pinfunction "1_1") (pintype "passive"))
      (node (ref "C44") (pin "1") (pinfunction "1_1") (pintype "passive"))
      (node (ref "C45") (pin "1") (pinfunction "1_1") (pintype "passive"))
      (node (ref "C46") (pin "1") (pinfunction "1_1") (pintype "passive"))
      (node (ref "C47") (pin "1") (pinfunction "1_1") (pintype "passive"))
      (node (ref "CN3") (pin "1") (pinfunction "1_1") (pintype "passive"))
      (node (ref "CN8") (pin "10") (pinfunction "10_10") (pintype "passive"))
      (node (ref "CN9") (pin "10") (pinfunction "10_10") (pintype "passive"))
      (node (ref "R10") (pin "1") (pinfunction "1_1") (pintype "passive"))
      (node (ref "R20") (pin "1") (pinfunction "1_1") (pintype "passive"))
      (node (ref "TP6") (pin "1") (pintype "passive"))
      (node (ref "U3") (pin "3") (pinfunction "~{WP}_3") (pintype "input"))
      (node (ref "U3") (pin "8") (pinfunction "VCC_8") (pintype "power_in"))
      (node (ref "U5") (pin "34") (pinfunction "AVDD_34") (pintype "power_in"))
      (node (ref "U5") (pin "39") (pinfunction "VREGVDD_39") (pintype "power_in"))
      (node (ref "U5") (pin "42") (pinfunction "IOVDD_42") (pintype "power_in"))
      (node (ref "U6") (pin "8") (pinfunction "VCC_8") (pintype "power_in"))
      (node (ref "U7") (pin "5") (pinfunction "OUT_5") (pintype "power_in"))
    )
    (net (code "2") (name "+4.0V") (class "Default")
      (node (ref "C10") (pin "1") (pinfunction "1_1") (pintype "passive"))
      (node (ref "C14") (pin "2") (pinfunction "2_2") (pintype "passive"))
      (node (ref "C8") (pin "2") (pinfunction "2_2") (pintype "passive"))
      (node (ref "C9") (pin "2") (pinfunction "2_2") (pintype "passive"))
      (node (ref "L7") (pin "2") (pinfunction "2_2") (pintype "passive"))
      (node (ref "L8") (pin "2") (pinfunction "2_2") (pintype "passive"))
      (node (ref "L9") (pin "2") (pinfunction "2_2") (pintype "passive"))
      (node (ref "R1") (pin "2") (pinfunction "2_2") (pintype "passive"))
      (node (ref "R5") (pin "2") (pinfunction "2_2") (pintype "passive"))
      (node (ref "U2") (pin "1") (pinfunction "OUT_1") (pintype "power_in"))
    )
    (net (code "3") (name "/ADC_CH1") (class "Default")
      (node (ref "C37") (pin "2") (pinfunction "2_2") (pintype "passive"))
      (node (ref "CN9") (pin "1") (pinfunction "1_1") (pintype "passive"))
      (node (ref "U5") (pin "31") (pinfunction "PB11_31") (pintype "bidirectional"))
    )
    (net (code "4") (name "/ADC_CH2") (class "Default")
      (node (ref "C38") (pin "2") (pinfunction "2_2") (pintype "passive"))
      (node (ref "CN9") (pin "3") (pinfunction "3_3") (pintype "passive"))
      (node (ref "U5") (pin "32") (pinfunction "PB12_32") (pintype "bidirectional"))
    )
    (net (code "5") (name "/ADC_CH3") (class "Default")
      (node (ref "C40") (pin "2") (pinfunction "2_2") (pintype "passive"))
      (node (ref "CN9") (pin "5") (pinfunction "5_5") (pintype "passive"))
      (node (ref "U5") (pin "33") (pinfunction "PB13_33") (pintype "bidirectional"))
    )
    (net (code "6") (name "/ADC_CH4") (class "Default")
      (node (ref "C35") (pin "2") (pinfunction "2_2") (pintype "passive"))
      (node (ref "CN9") (pin "7") (pinfunction "7_7") (pintype "passive"))
      (node (ref "R13") (pin "1") (pinfunction "1_1") (pintype "passive"))
      (node (ref "R9") (pin "2") (pinfunction "2_2") (pintype "passive"))
      (node (ref "U5") (pin "30") (pinfunction "PA5_30") (pintype "bidirectional"))
    )
    (net (code "7") (name "/ADC_CH5") (class "Default")
      (node (ref "C33") (pin "2") (pinfunction "2_2") (pintype "passive"))
      (node (ref "CN9") (pin "9") (pinfunction "9_9") (pintype "passive"))
      (node (ref "R11") (pin "1") (pinfunction "1_1") (pintype "passive"))
      (node (ref "R39") (pin "2") (pinfunction "2_2") (pintype "passive"))
      (node (ref "U5") (pin "29") (pinfunction "PA4_29") (pintype "bidirectional"))
    )
    (net (code "8") (name "/ANT") (class "Default")
      (node (ref "C1") (pin "1") (pinfunction "1_1") (pintype "passive"))
      (node (ref "CN1") (pin "5") (pinfunction "SIG_5") (pintype "passive"))
    )
    (net (code "9") (name "/DVDD_DECOUPLE") (class "Default")
      (node (ref "C43") (pin "1") (pinfunction "1_1") (pintype "passive"))
      (node (ref "U5") (pin "41") (pinfunction "DECOUPLE_41") (pintype "power_in"))
    )
    (net (code "10") (name "/FEM_ANTSEL") (class "Default")
      (node (ref "R4") (pin "2") (pinfunction "2_2") (pintype "passive"))
      (node (ref "U5") (pin "24") (pinfunction "PD15_24") (pintype "bidirectional"))
    )
    (net (code "11") (name "/FEM_LNAEN") (class "Default")
      (node (ref "R6") (pin "2") (pinfunction "2_2") (pintype "passive"))
      (node (ref "U5") (pin "22") (pinfunction "PD13_22") (pintype "bidirectional"))
    )
    (net (code "12") (name "/FEM_PAEN") (class "Default")
      (node (ref "R7") (pin "2") (pinfunction "2_2") (pintype "passive"))
      (node (ref "U5") (pin "23") (pinfunction "PD14_23") (pintype "bidirectional"))
    )
    (net (code "13") (name "/FLASH_nCS") (class "Default")
      (node (ref "R10") (pin "2") (pinfunction "2_2") (pintype "passive"))
      (node (ref "U3") (pin "1") (pinfunction "~{CS}_1") (pintype "input"))
      (node (ref "U5") (pin "28") (pinfunction "PA3_28") (pintype "bidirectional"))
    )
    (net (code "14") (name "/FLASH_nRESET") (class "Default")
      (node (ref "R20") (pin "2") (pinfunction "2_2") (pintype "passive"))
      (node (ref "U3") (pin "7") (pinfunction "nRESET_7") (pintype "input"))
      (node (ref "U5") (pin "4") (pinfunction "PF3_4") (pintype "bidirectional"))
    )
    (net (code "15") (name "/GPIO0") (class "Default")
      (node (ref "CN8") (pin "4") (pinfunction "4_4") (pintype "passive"))
      (node (ref "U5") (pin "45") (pinfunction "PC8_45") (pintype "bidirectional"))
    )
    (net (code "16") (name "/GPIO1") (class "Default")
      (node (ref "CN8") (pin "6") (pinfunction "6_6") (pintype "passive"))
      (node (ref "U5") (pin "46") (pinfunction "PC9_46") (pintype "bidirectional"))
    )
    (net (code "17") (name "/IN0") (class "Default")
      (node (ref "CN11") (pin "1L") (pinfunction "1_1L") (pintype "passive"))
      (node (ref "R9") (pin "1") (pinfunction "1_1") (pintype "passive"))
    )
    (net (code "18") (name "/IN1") (class "Default")
      (node (ref "CN11") (pin "2L") (pinfunction "2_2L") (pintype "passive"))
      (node (ref "R39") (pin "1") (pinfunction "1_1") (pintype "passive"))
    )
    (net (code "19") (name "/LED") (class "Default")
      (node (ref "R30") (pin "1") (pinfunction "1_1") (pintype "passive"))
      (node (ref "U5") (pin "44") (pinfunction "PC7_44") (pintype "bidirectional"))
    )
    (net (code "20") (name "/LFXTAL_N") (class "Default")
      (node (ref "U5") (pin "35") (pinfunction "PB14_35") (pintype "bidirectional"))
      (node (ref "Y2") (pin "2") (pinfunction "S2_2") (pintype "passive"))
    )
    (net (code "21") (name "/LFXTAL_P") (class "Default")
      (node (ref "U5") (pin "36") (pinfunction "PB15_36") (pintype "bidirectional"))
      (node (ref "Y2") (pin "1") (pinfunction "S1_1") (pintype "passive"))
    )
    (net (code "22") (name "/MISO") (class "Default")
      (node (ref "U3") (pin "2") (pinfunction "SO_2") (pintype "tri_state"))
      (node (ref "U5") (pin "26") (pinfunction "PA1_26") (pintype "bidirectional"))
    )
    (net (code "23") (name "/MOSI") (class "Default")
      (node (ref "U3") (pin "5") (pinfunction "SI_5") (pintype "input"))
      (node (ref "U5") (pin "25") (pinfunction "PA0_25") (pintype "bidirectional"))
    )
    (net (code "24") (name "/NCP_CTS") (class "Default")
      (node (ref "CN8") (pin "3") (pinfunction "3_3") (pintype "passive"))
      (node (ref "U5") (pin "7") (pinfunction "PF6_7") (pintype "bidirectional"))
    )
    (net (code "25") (name "/NCP_PWR") (class "Default")
      (node (ref "CN9") (pin "2") (pinfunction "2_2") (pintype "passive"))
      (node (ref "R8") (pin "1") (pinfunction "1_1") (pintype "passive"))
      (node (ref "U2") (pin "5") (pinfunction "EN_5") (pintype "input"))
      (node (ref "U7") (pin "3") (pinfunction "EN_3") (pintype "input"))
    )
    (net (code "26") (name "/NCP_RTS") (class "Default")
      (node (ref "CN8") (pin "9") (pinfunction "9_9") (pintype "passive"))
      (node (ref "U5") (pin "8") (pinfunction "PF7_8") (pintype "bidirectional"))
    )
    (net (code "27") (name "/NCP_RX") (class "Default")
      (node (ref "CN8") (pin "5") (pinfunction "5_5") (pintype "passive"))
      (node (ref "U5") (pin "6") (pinfunction "PF5_6") (pintype "bidirectional"))
    )
    (net (code "28") (name "/NCP_TX") (class "Default")
      (node (ref "CN8") (pin "7") (pinfunction "7_7") (pintype "passive"))
      (node (ref "U5") (pin "5") (pinfunction "PF4_5") (pintype "bidirectional"))
    )
    (net (code "29") (name "/PAVDD") (class "Default")
      (node (ref "C24") (pin "2") (pinfunction "2_2") (pintype "passive"))
      (node (ref "C25") (pin "2") (pinfunction "2_2") (pintype "passive"))
      (node (ref "FB1") (pin "2") (pinfunction "2_2") (pintype "passive"))
      (node (ref "R12") (pin "1") (pinfunction "1_1") (pintype "passive"))
      (node (ref "T1") (pin "2") (pinfunction "2_2") (pintype "passive"))
    )
    (net (code "30") (name "/PAVDD24") (class "Default")
      (node (ref "C31") (pin "2") (pinfunction "2_2") (pintype "passive"))
      (node (ref "R12") (pin "2") (pinfunction "2_2") (pintype "passive"))
      (node (ref "U5") (pin "21") (pinfunction "PD12_21") (pintype "bidirectional"))
    )
    (net (code "31") (name "/RF1") (class "Default")
      (node (ref "C23") (pin "1") (pinfunction "1_1") (pintype "passive"))
      (node (ref "L11") (pin "1") (pinfunction "1_1") (pintype "passive"))
      (node (ref "T1") (pin "1") (pinfunction "1_1") (pintype "passive"))
    )
    (net (code "32") (name "/RF2") (class "Default")
      (node (ref "C21") (pin "1") (pinfunction "1_1") (pintype "passive"))
      (node (ref "L10") (pin "1") (pinfunction "1_1") (pintype "passive"))
      (node (ref "L11") (pin "2") (pinfunction "2_2") (pintype "passive"))
    )
    (net (code "33") (name "/RF3") (class "Default")
      (node (ref "C19") (pin "1") (pinfunction "1_1") (pintype "passive"))
      (node (ref "C20") (pin "1") (pinfunction "1_1") (pintype "passive"))
      (node (ref "L10") (pin "2") (pinfunction "2_2") (pintype "passive"))
    )
    (net (code "34") (name "/RF4") (class "Default")
      (node (ref "C17") (pin "2") (pinfunction "2_2") (pintype "passive"))
      (node (ref "C18") (pin "2") (pinfunction "2_2") (pintype "passive"))
      (node (ref "C19") (pin "2") (pinfunction "2_2") (pintype "passive"))
    )
    (net (code "35") (name "/RF5") (class "Default")
      (node (ref "C18") (pin "1") (pinfunction "1_1") (pintype "passive"))
      (node (ref "CN6") (pin "1") (pinfunction "SIG_1") (pintype "passive"))
    )
    (net (code "36") (name "/RFDIFF_N") (class "Default")
      (node (ref "C26") (pin "2") (pinfunction "2_2") (pintype "passive"))
      (node (ref "L12") (pin "2") (pinfunction "2_2") (pintype "passive"))
      (node (ref "T1") (pin "3") (pinfunction "3_3") (pintype "passive"))
    )
    (net (code "37") (name "/RFDIFF_P") (class "Default")
      (node (ref "C26") (pin "1") (pinfunction "1_1") (pintype "passive"))
      (node (ref "L13") (pin "2") (pinfunction "2_2") (pintype "passive"))
      (node (ref "T1") (pin "4") (pinfunction "4_4") (pintype "passive"))
    )
    (net (code "38") (name "/RFI_N") (class "Default")
      (node (ref "C29") (pin "2") (pinfunction "2_2") (pintype "passive"))
      (node (ref "L15") (pin "1") (pinfunction "1_1") (pintype "passive"))
      (node (ref "U5") (pin "16") (pinfunction "SUBGRFI_N_16") (pintype "input"))
    )
    (net (code "39") (name "/RFI_P") (class "Default")
      (node (ref "C30") (pin "2") (pinfunction "2_2") (pintype "passive"))
      (node (ref "L15") (pin "2") (pinfunction "2_2") (pintype "passive"))
      (node (ref "U5") (pin "15") (pinfunction "SUBGRFI_P_15") (pintype "input"))
    )
    (net (code "40") (name "/RFO_N") (class "Default")
      (node (ref "C29") (pin "1") (pinfunction "1_1") (pintype "passive"))
      (node (ref "L12") (pin "1") (pinfunction "1_1") (pintype "passive"))
      (node (ref "U5") (pin "14") (pinfunction "SUBGRFO_N_14") (pintype "output"))
    )
    (net (code "41") (name "/RFO_P") (class "Default")
      (node (ref "C30") (pin "1") (pinfunction "1_1") (pintype "passive"))
      (node (ref "L13") (pin "1") (pinfunction "1_1") (pintype "passive"))
      (node (ref "U5") (pin "13") (pinfunction "SUBGRFO_P_13") (pintype "output"))
    )
    (net (code "42") (name "/RF_ANT1") (class "Default")
      (node (ref "C1") (pin "2") (pinfunction "2_2") (pintype "passive"))
      (node (ref "C2") (pin "1") (pinfunction "1_1") (pintype "passive"))
      (node (ref "L1") (pin "2") (pinfunction "2_2") (pintype "passive"))
    )
    (net (code "43") (name "/RF_ANT1_1") (class "Default")
      (node (ref "C3") (pin "2") (pinfunction "2_2") (pintype "passive"))
      (node (ref "L1") (pin "1") (pinfunction "1_1") (pintype "passive"))
      (node (ref "L2") (pin "2") (pinfunction "2_2") (pintype "passive"))
    )
    (net (code "44") (name "/RF_ANT1_2") (class "Default")
      (node (ref "L2") (pin "1") (pinfunction "1_1") (pintype "passive"))
      (node (ref "U1") (pin "14") (pinfunction "ANT1_14") (pintype "bidirectional"))
    )
    (net (code "45") (name "/RF_ANT2") (class "Default")
      (node (ref "CN5") (pin "1") (pinfunction "SIG_1") (pintype "passive"))
      (node (ref "L6") (pin "2") (pinfunction "2_2") (pintype "passive"))
    )
    (net (code "46") (name "/RF_ANT2_1") (class "Default")
      (node (ref "C6") (pin "2") (pinfunction "2_2") (pintype "passive"))
      (node (ref "L5") (pin "2") (pinfunction "2_2") (pintype "passive"))
      (node (ref "L6") (pin "1") (pinfunction "1_1") (pintype "passive"))
    )
    (net (code "47") (name "/RF_ANT2_2") (class "Default")
      (node (ref "L5") (pin "1") (pinfunction "1_1") (pintype "passive"))
      (node (ref "U1") (pin "12") (pinfunction "ANT2_12") (pintype "bidirectional"))
    )
    (net (code "48") (name "/RF_LNA1") (class "Default")
      (node (ref "R3") (pin "1") (pinfunction "1_1") (pintype "passive"))
      (node (ref "U1") (pin "11") (pinfunction "RX_FLT_11") (pintype "output"))
    )
    (net (code "49") (name "/RF_LNA2") (class "Default")
      (node (ref "R3") (pin "2") (pinfunction "2_2") (pintype "passive"))
      (node (ref "U1") (pin "9") (pinfunction "LNA_IN_9") (pintype "input"))
    )
    (net (code "50") (name "/RF_PA1") (class "Default")
      (node (ref "C16") (pin "2") (pinfunction "2_2") (pintype "passive"))
      (node (ref "U1") (pin "5") (pinfunction "TX_FLT_5") (pintype "output"))
    )
    (net (code "51") (name "/RF_PA2") (class "Default")
      (node (ref "C16") (pin "1") (pinfunction "1_1") (pintype "passive"))
      (node (ref "U1") (pin "2") (pinfunction "PA_IN_2") (pintype "input"))
    )
    (net (code "52") (name "/RF_PA3") (class "Default")
      (node (ref "C7") (pin "1") (pinfunction "1_1") (pintype "passive"))
      (node (ref "L4") (pin "1") (pinfunction "1_1") (pintype "passive"))
      (node (ref "U1") (pin "20") (pinfunction "PA_OUT_20") (pintype "output"))
    )
    (net (code "53") (name "/RF_PA4") (class "Default")
      (node (ref "C5") (pin "1") (pinfunction "1_1") (pintype "passive"))
      (node (ref "L3") (pin "2") (pinfunction "2_2") (pintype "passive"))
      (node (ref "L4") (pin "2") (pinfunction "2_2") (pintype "passive"))
    )
    (net (code "54") (name "/RF_PA5") (class "Default")
      (node (ref "C4") (pin "1") (pinfunction "1_1") (pintype "passive"))
      (node (ref "L3") (pin "1") (pinfunction "1_1") (pintype "passive"))
      (node (ref "U1") (pin "16") (pinfunction "TX_IN_16") (pintype "input"))
    )
    (net (code "55") (name "/RS485_A") (class "Default")
      (node (ref "CN10") (pin "2L") (pinfunction "2_2L") (pintype "passive"))
      (node (ref "R38") (pin "1") (pinfunction "1_1") (pintype "passive"))
      (node (ref "TVS1") (pin "2") (pinfunction "2_2") (pintype "passive"))
    )
    (net (code "56") (name "/RS485_B") (class "Default")
      (node (ref "CN10") (pin "3L") (pinfunction "3_3L") (pintype "passive"))
      (node (ref "R37") (pin "1") (pinfunction "1_1") (pintype "passive"))
      (node (ref "TVS1") (pin "1") (pinfunction "1_1") (pintype "passive"))
    )
    (net (code "57") (name "/RS485_DE") (class "Default")
      (node (ref "R21") (pin "2") (pinfunction "2_2") (pintype "passive"))
      (node (ref "U5") (pin "3") (pinfunction "PF2_3") (pintype "bidirectional"))
      (node (ref "U6") (pin "3") (pinfunction "DE_3") (pintype "input"))
    )
    (net (code "58") (name "/RS485_N") (class "Default")
      (node (ref "R37") (pin "2") (pinfunction "2_2") (pintype "passive"))
      (node (ref "U6") (pin "7") (pinfunction "~{B}_7") (pintype "bidirectional"))
    )
    (net (code "59") (name "/RS485_P") (class "Default")
      (node (ref "R38") (pin "2") (pinfunction "2_2") (pintype "passive"))
      (node (ref "U6") (pin "6") (pinfunction "A_6") (pintype "bidirectional"))
    )
    (net (code "60") (name "/RS485_nRE") (class "Default")
      (node (ref "U5") (pin "43") (pinfunction "PC6_43") (pintype "bidirectional"))
      (node (ref "U6") (pin "2") (pinfunction "~{RE}_2") (pintype "input"))
    )
    (net (code "61") (name "/SCK") (class "Default")
      (node (ref "U3") (pin "6") (pinfunction "SCK_6") (pintype "input"))
      (node (ref "U5") (pin "27") (pinfunction "PA2_27") (pintype "bidirectional"))
    )
    (net (code "62") (name "/SWCLK") (class "Default")
      (node (ref "R16") (pin "2") (pinfunction "2_2") (pintype "passive"))
      (node (ref "U5") (pin "1") (pinfunction "PF0_1") (pintype "bidirectional"))
    )
    (net (code "63") (name "/SWDCLK_CN") (class "Default")
      (node (ref "CN3") (pin "4") (pinfunction "4_4") (pintype "passive"))
      (node (ref "R16") (pin "1") (pinfunction "1_1") (pintype "passive"))
      (node (ref "TP2") (pin "1") (pintype "passive"))
    )
    (net (code "64") (name "/SWDIO") (class "Default")
      (node (ref "R15") (pin "2") (pinfunction "2_2") (pintype "passive"))
      (node (ref "U5") (pin "2") (pinfunction "PF1_2") (pintype "bidirectional"))
    )
    (net (code "65") (name "/SWDIO_CN") (class "Default")
      (node (ref "CN3") (pin "2") (pinfunction "2_2") (pintype "passive"))
      (node (ref "R15") (pin "1") (pinfunction "1_1") (pintype "passive"))
      (node (ref "TP1") (pin "1") (pintype "passive"))
    )
    (net (code "66") (name "/UART_RX") (class "Default")
      (node (ref "CN9") (pin "4") (pinfunction "4_4") (pintype "passive"))
      (node (ref "R18") (pin "2") (pinfunction "2_2") (pintype "passive"))
      (node (ref "U5") (pin "47") (pinfunction "PC10_47") (pintype "bidirectional"))
      (node (ref "U6") (pin "1") (pinfunction "R_1") (pintype "tri_state"))
    )
    (net (code "67") (name "/UART_RX_CN") (class "Default")
      (node (ref "CN3") (pin "9") (pinfunction "9_9") (pintype "passive"))
      (node (ref "R18") (pin "1") (pinfunction "1_1") (pintype "passive"))
      (node (ref "TP4") (pin "1") (pintype "passive"))
    )
    (net (code "68") (name "/UART_TX") (class "Default")
      (node (ref "CN9") (pin "6") (pinfunction "6_6") (pintype "passive"))
      (node (ref "R19") (pin "2") (pinfunction "2_2") (pintype "passive"))
      (node (ref "U5") (pin "48") (pinfunction "PC11_48") (pintype "bidirectional"))
      (node (ref "U6") (pin "4") (pinfunction "D_4") (pintype "input"))
    )
    (net (code "69") (name "/UART_TX_CN") (class "Default")
      (node (ref "CN3") (pin "7") (pinfunction "7_7") (pintype "passive"))
      (node (ref "R19") (pin "1") (pinfunction "1_1") (pintype "passive"))
      (node (ref "TP5") (pin "1") (pintype "passive"))
    )
    (net (code "70") (name "/VDCDC") (class "Default")
      (node (ref "C39") (pin "1") (pinfunction "1_1") (pintype "passive"))
      (node (ref "C42") (pin "2") (pinfunction "2_2") (pintype "passive"))
      (node (ref "FB1") (pin "1") (pinfunction "1_1") (pintype "passive"))
      (node (ref "FB2") (pin "2") (pinfunction "2_2") (pintype "passive"))
      (node (ref "L16") (pin "2") (pinfunction "2_2") (pintype "passive"))
      (node (ref "U5") (pin "40") (pinfunction "DVDD_40") (pintype "power_in"))
    )
    (net (code "71") (name "/VDDRF") (class "Default")
      (node (ref "C34") (pin "2") (pinfunction "2_2") (pintype "passive"))
      (node (ref "FB2") (pin "1") (pinfunction "1_1") (pintype "passive"))
      (node (ref "U5") (pin "9") (pinfunction "RFVDD_9") (pintype "power_in"))
    )
    (net (code "72") (name "/VREGSW") (class "Default")
      (node (ref "L16") (pin "1") (pinfunction "1_1") (pintype "passive"))
      (node (ref "U5") (pin "38") (pinfunction "VREGSW_38") (pintype "power_in"))
    )
    (net (code "73") (name "/XIN") (class "Default")
      (node (ref "U5") (pin "10") (pinfunction "HFXTAL_N_10") (pintype "input"))
      (node (ref "Y1") (pin "1") (pinfunction "S1_1") (pintype "passive"))
    )
    (net (code "74") (name "/XOUT") (class "Default")
      (node (ref "U5") (pin "11") (pinfunction "HFXTAL_P_11") (pintype "output"))
      (node (ref "Y1") (pin "3") (pinfunction "S2_3") (pintype "passive"))
    )
    (net (code "75") (name "/nRESET") (class "Default")
      (node (ref "C27") (pin "2") (pinfunction "2_2") (pintype "passive"))
      (node (ref "CN8") (pin "8") (pinfunction "8_8") (pintype "passive"))
      (node (ref "R17") (pin "2") (pinfunction "2_2") (pintype "passive"))
      (node (ref "U5") (pin "12") (pinfunction "nRESET_12") (pintype "input"))
    )
    (net (code "76") (name "/nRESET_CN") (class "Default")
      (node (ref "CN3") (pin "10") (pinfunction "10_10") (pintype "passive"))
      (node (ref "R17") (pin "1") (pinfunction "1_1") (pintype "passive"))
      (node (ref "TP3") (pin "1") (pintype "passive"))
    )
    (net (code "77") (name "GND") (class "Default")
      (node (ref "C10") (pin "2") (pinfunction "2_2") (pintype "passive"))
      (node (ref "C11") (pin "1") (pinfunction "1_1") (pintype "passive"))
      (node (ref "C12") (pin "1") (pinfunction "1_1") (pintype "passive"))
      (node (ref "C13") (pin "2") (pinfunction "2_2") (pintype "passive"))
      (node (ref "C14") (pin "1") (pinfunction "1_1") (pintype "passive"))
      (node (ref "C15") (pin "2") (pinfunction "2_2") (pintype "passive"))
      (node (ref "C20") (pin "2") (pinfunction "2_2") (pintype "passive"))
      (node (ref "C21") (pin "2") (pinfunction "2_2") (pintype "passive"))
      (node (ref "C23") (pin "2") (pinfunction "2_2") (pintype "passive"))
      (node (ref "C24") (pin "1") (pinfunction "1_1") (pintype "passive"))
      (node (ref "C25") (pin "1") (pinfunction "1_1") (pintype "passive"))
      (node (ref "C27") (pin "1") (pinfunction "1_1") (pintype "passive"))
      (node (ref "C3") (pin "1") (pinfunction "1_1") (pintype "passive"))
      (node (ref "C31") (pin "1") (pinfunction "1_1") (pintype "passive"))
      (node (ref "C33") (pin "1") (pinfunction "1_1") (pintype "passive"))
      (node (ref "C34") (pin "1") (pinfunction "1_1") (pintype "passive"))
      (node (ref "C35") (pin "1") (pinfunction "1_1") (pintype "passive"))
      (node (ref "C36") (pin "2") (pinfunction "2_2") (pintype "passive"))
      (node (ref "C37") (pin "1") (pinfunction "1_1") (pintype "passive"))
      (node (ref "C38") (pin "1") (pinfunction "1_1") (pintype "passive"))
      (node (ref "C39") (pin "2") (pinfunction "2_2") (pintype "passive"))
      (node (ref "C4") (pin "2") (pinfunction "2_2") (pintype "passive"))
      (node (ref "C40") (pin "1") (pinfunction "1_1") (pintype "passive"))
      (node (ref "C42") (pin "1") (pinfunction "1_1") (pintype "passive"))
      (node (ref "C43") (pin "2") (pinfunction "2_2") (pintype "passive"))
      (node (ref "C44") (pin "2") (pinfunction "2_2") (pintype "passive"))
      (node (ref "C45") (pin "2") (pinfunction "2_2") (pintype "passive"))
      (node (ref "C46") (pin "2") (pinfunction "2_2") (pintype "passive"))
      (node (ref "C47") (pin "2") (pinfunction "2_2") (pintype "passive"))
      (node (ref "C5") (pin "2") (pinfunction "2_2") (pintype "passive"))
      (node (ref "C6") (pin "1") (pinfunction "1_1") (pintype "passive"))
      (node (ref "C7") (pin "2") (pinfunction "2_2") (pintype "passive"))
      (node (ref "C8") (pin "1") (pinfunction "1_1") (pintype "passive"))
      (node (ref "C9") (pin "1") (pinfunction "1_1") (pintype "passive"))
      (node (ref "CN1") (pin "1") (pinfunction "GND_1") (pintype "passive"))
      (node (ref "CN1") (pin "2") (pinfunction "GND_2") (pintype "passive"))
      (node (ref "CN1") (pin "3") (pinfunction "GND_3") (pintype "passive"))
      (node (ref "CN1") (pin "4") (pinfunction "GND_4") (pintype "passive"))
      (node (ref "CN10") (pin "1L") (pinfunction "1_1L") (pintype "passive"))
      (node (ref "CN2") (pin "2L") (pinfunction "2_2L") (pintype "passive"))
      (node (ref "CN3") (pin "3") (pinfunction "3_3") (pintype "passive"))
      (node (ref "CN3") (pin "5") (pinfunction "5_5") (pintype "passive"))
      (node (ref "CN4") (pin "2") (pinfunction "GND_2") (pintype "passive"))
      (node (ref "CN4") (pin "3") (pinfunction "GND_3") (pintype "passive"))
      (node (ref "CN5") (pin "2") (pinfunction "GND_2") (pintype "passive"))
      (node (ref "CN5") (pin "3") (pinfunction "GND_3") (pintype "passive"))
      (node (ref "CN6") (pin "2") (pinfunction "GND_2") (pintype "passive"))
      (node (ref "CN6") (pin "3") (pinfunction "GND_3") (pintype "passive"))
      (node (ref "CN8") (pin "1") (pinfunction "1_1") (pintype "passive"))
      (node (ref "CN9") (pin "8") (pinfunction "8_8") (pintype "passive"))
      (node (ref "LED1") (pin "2") (pinfunction "ANODE_2") (pintype "passive"))
      (node (ref "R11") (pin "2") (pinfunction "2_2") (pintype "passive"))
      (node (ref "R13") (pin "2") (pinfunction "2_2") (pintype "passive"))
      (node (ref "R14") (pin "1") (pinfunction "1_1") (pintype "passive"))
      (node (ref "R2") (pin "1") (pinfunction "1_1") (pintype "passive"))
      (node (ref "R21") (pin "1") (pinfunction "1_1") (pintype "passive"))
      (node (ref "T1") (pin "5") (pinfunction "5_5") (pintype "passive"))
      (node (ref "TP7") (pin "1") (pintype "passive"))
      (node (ref "TVS1") (pin "3") (pinfunction "3_3") (pintype "passive"))
      (node (ref "U1") (pin "0") (pinfunction "EP_0") (pintype "power_in"))
      (node (ref "U1") (pin "10") (pinfunction "NC_10") (pintype "passive"))
      (node (ref "U1") (pin "13") (pinfunction "NC_13") (pintype "passive"))
      (node (ref "U1") (pin "15") (pinfunction "NC_15") (pintype "passive"))
      (node (ref "U1") (pin "17") (pinfunction "NC_17") (pintype "passive"))
      (node (ref "U1") (pin "18") (pinfunction "NC_18") (pintype "passive"))
      (node (ref "U1") (pin "19") (pinfunction "NC_19") (pintype "passive"))
      (node (ref "U1") (pin "22") (pinfunction "NC_22") (pintype "passive"))
      (node (ref "U1") (pin "8") (pinfunction "GND_8") (pintype "power_in"))
      (node (ref "U2") (pin "0") (pinfunction "EP_0") (pintype "power_in"))
      (node (ref "U2") (pin "4") (pinfunction "GND_4") (pintype "power_in"))
      (node (ref "U3") (pin "4") (pinfunction "GND_4") (pintype "power_in"))
      (node (ref "U5") (pin "0") (pinfunction "GND_0") (pintype "power_in"))
      (node (ref "U5") (pin "17") (pinfunction "RFVSS_17") (pintype "power_in"))
      (node (ref "U5") (pin "18") (pinfunction "PD9_18") (pintype "bidirectional"))
      (node (ref "U5") (pin "19") (pinfunction "PD10_19") (pintype "bidirectional"))
      (node (ref "U5") (pin "37") (pinfunction "VREGVSS_37") (pintype "power_in"))
      (node (ref "U6") (pin "5") (pinfunction "GND_5") (pintype "power_in"))
      (node (ref "U7") (pin "2") (pinfunction "GND_2") (pintype "power_in"))
      (node (ref "X1") (pin "1") (pinfunction "PIN_1") (pintype "passive"))
      (node (ref "Y1") (pin "2") (pinfunction "GND_2") (pintype "passive"))
      (node (ref "Y1") (pin "4") (pinfunction "GND_4") (pintype "passive"))
    )
    (net (code "78") (name "Net-(CN4-SIG)") (class "Default")
      (node (ref "C2") (pin "2") (pinfunction "2_2") (pintype "passive"))
      (node (ref "CN4") (pin "1") (pinfunction "SIG_1") (pintype "passive"))
    )
    (net (code "79") (name "Net-(LED1-CATHODE)") (class "Default")
      (node (ref "LED1") (pin "1") (pinfunction "CATHODE_1") (pintype "passive"))
      (node (ref "R30") (pin "2") (pinfunction "2_2") (pintype "passive"))
    )
    (net (code "80") (name "Net-(U1-ANT_SEL)") (class "Default")
      (node (ref "R4") (pin "1") (pinfunction "1_1") (pintype "passive"))
      (node (ref "U1") (pin "7") (pinfunction "ANT_SEL_7") (pintype "input"))
    )
    (net (code "81") (name "Net-(U1-CPS)") (class "Default")
      (node (ref "R6") (pin "1") (pinfunction "1_1") (pintype "passive"))
      (node (ref "U1") (pin "3") (pinfunction "CPS_3") (pintype "input"))
    )
    (net (code "82") (name "Net-(U1-CSD)") (class "Default")
      (node (ref "R5") (pin "1") (pinfunction "1_1") (pintype "passive"))
      (node (ref "U1") (pin "1") (pinfunction "CSD_1") (pintype "input"))
    )
    (net (code "83") (name "Net-(U1-CTX)") (class "Default")
      (node (ref "R7") (pin "1") (pinfunction "1_1") (pintype "passive"))
      (node (ref "U1") (pin "4") (pinfunction "CTX_4") (pintype "input"))
    )
    (net (code "84") (name "Net-(U1-TR)") (class "Default")
      (node (ref "C17") (pin "1") (pinfunction "1_1") (pintype "passive"))
      (node (ref "U1") (pin "6") (pinfunction "TR_6") (pintype "bidirectional"))
    )
    (net (code "85") (name "Net-(U1-VCC0)") (class "Default")
      (node (ref "C11") (pin "2") (pinfunction "2_2") (pintype "passive"))
      (node (ref "L8") (pin "1") (pinfunction "1_1") (pintype "passive"))
      (node (ref "U1") (pin "23") (pinfunction "VCC0_23") (pintype "power_in"))
    )
    (net (code "86") (name "Net-(U1-VCC1)") (class "Default")
      (node (ref "C12") (pin "2") (pinfunction "2_2") (pintype "passive"))
      (node (ref "L9") (pin "1") (pinfunction "1_1") (pintype "passive"))
      (node (ref "U1") (pin "24") (pinfunction "VCC1_24") (pintype "power_in"))
    )
    (net (code "87") (name "Net-(U1-VCC2)") (class "Default")
      (node (ref "L7") (pin "1") (pinfunction "1_1") (pintype "passive"))
      (node (ref "U1") (pin "21") (pinfunction "VCC2_21") (pintype "power_in"))
    )
    (net (code "88") (name "Net-(U2-FB)") (class "Default")
      (node (ref "R1") (pin "1") (pinfunction "1_1") (pintype "passive"))
      (node (ref "R14") (pin "2") (pinfunction "2_2") (pintype "passive"))
      (node (ref "R2") (pin "2") (pinfunction "2_2") (pintype "passive"))
      (node (ref "U2") (pin "3") (pinfunction "FB_3") (pintype "input"))
    )
    (net (code "89") (name "VIN") (class "Default")
      (node (ref "C15") (pin "1") (pinfunction "1_1") (pintype "passive"))
      (node (ref "CN2") (pin "1L") (pinfunction "1_1L") (pintype "passive"))
      (node (ref "CN8") (pin "2") (pinfunction "2_2") (pintype "passive"))
      (node (ref "R8") (pin "2") (pinfunction "2_2") (pintype "passive"))
      (node (ref "U2") (pin "8") (pinfunction "IN_8") (pintype "passive"))
      (node (ref "U7") (pin "1") (pinfunction "IN_1") (pintype "power_in"))
    )
    (net (code "90") (name "unconnected-(CN3-Pad6)") (class "Default")
      (node (ref "CN3") (pin "6") (pinfunction "6_6") (pintype "passive+no_connect"))
    )
    (net (code "91") (name "unconnected-(CN3-Pad8)") (class "Default")
      (node (ref "CN3") (pin "8") (pinfunction "8_8") (pintype "passive+no_connect"))
    )
    (net (code "92") (name "unconnected-(U2-NC-Pad2)") (class "Default")
      (node (ref "U2") (pin "2") (pinfunction "NC_2") (pintype "passive+no_connect"))
    )
    (net (code "93") (name "unconnected-(U2-NC-Pad6)") (class "Default")
      (node (ref "U2") (pin "6") (pinfunction "NC_6") (pintype "passive+no_connect"))
    )
    (net (code "94") (name "unconnected-(U2-NC-Pad7)") (class "Default")
      (node (ref "U2") (pin "7") (pinfunction "NC_7") (pintype "passive+no_connect"))
    )
    (net (code "95") (name "unconnected-(U5-PD11-Pad20)") (class "Default")
      (node (ref "U5") (pin "20") (pinfunction "PD11_20") (pintype "bidirectional"))
    )
    (net (code "96") (name "unconnected-(U7-NC-Pad4)") (class "Default")
      (node (ref "U7") (pin "4") (pinfunction "NC_4") (pintype "tri_state+no_connect"))
    )
  )
)
